# Differential_Amplifier.net
KiCad netlist of a schematic drawn in Altium Designer
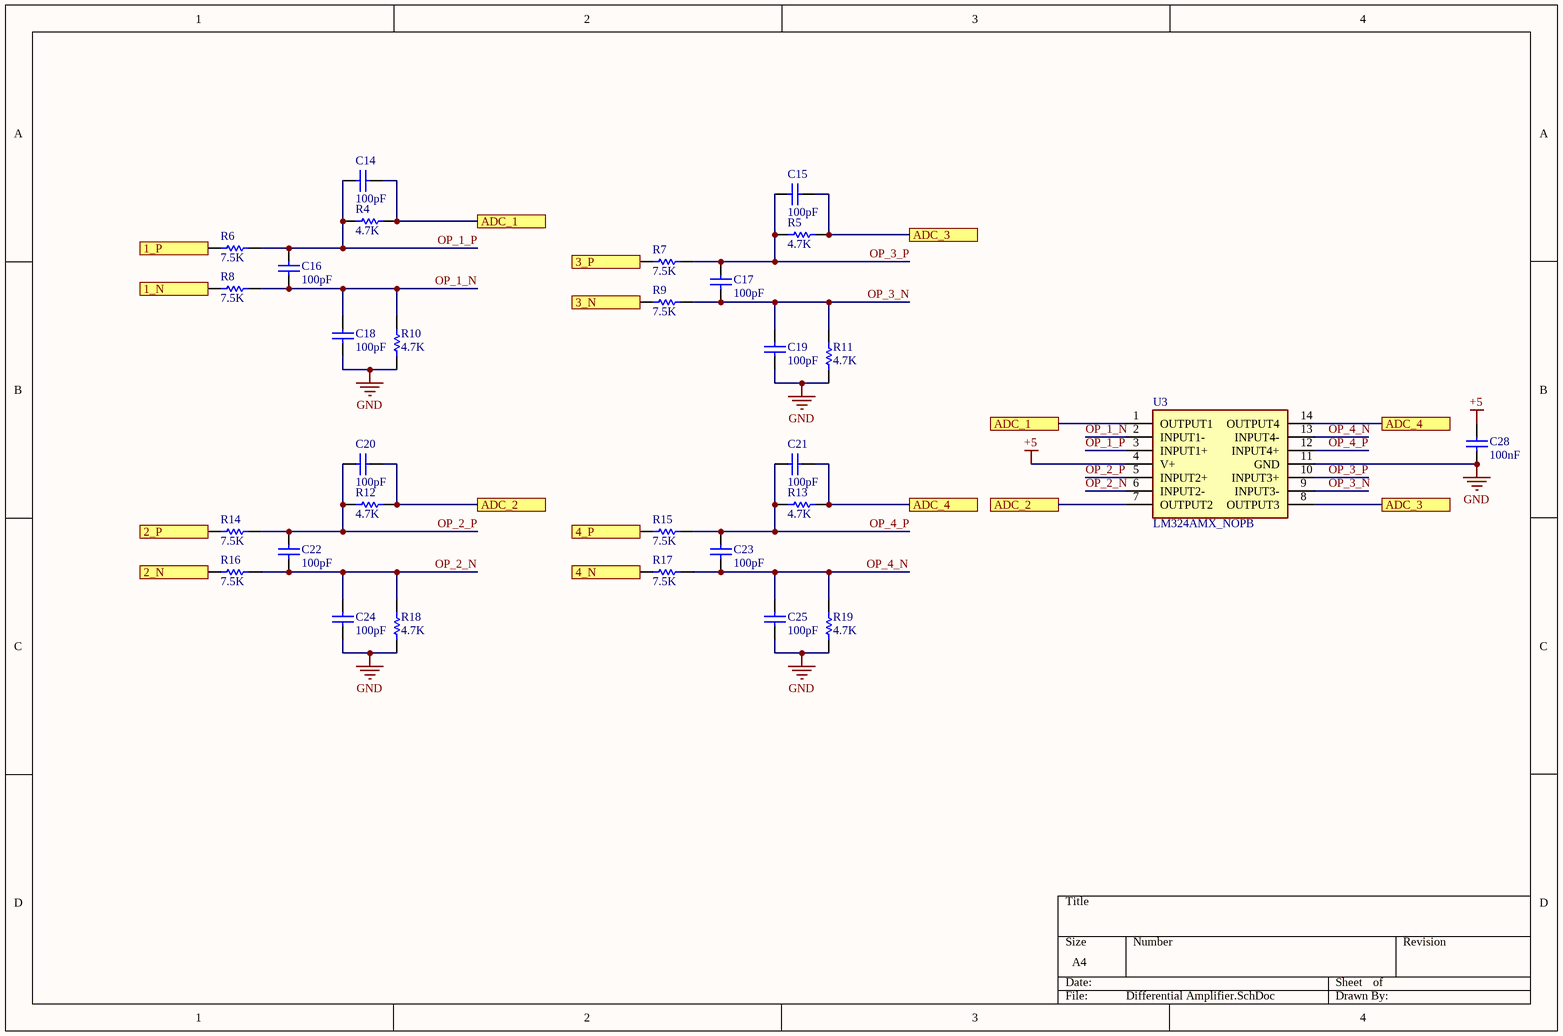
[diagram p0: Differential Amplifier.SchDoc]

(export (version "E")
  (design (tool "Eeschema 10.0.6"))
  (components
    (comp (ref "C14")
      (value "100pF")
      (footprint "C0805")
      (description "C0805C104K8RACTU. 0.1µF ±10% 10V Ceramic Capacitor X7R 0805 (2012 Metric)")
      (fields (field (name "Comment") "10V") (field (name "PUBLISHER") "Altium Limited"))
      (libsource (lib "Miscellaneous Devices") (part "Cap"))
    )
    (comp (ref "C15")
      (value "100pF")
      (footprint "C0805")
      (description "C0805C104K8RACTU. 0.1µF ±10% 10V Ceramic Capacitor X7R 0805 (2012 Metric)")
      (fields (field (name "Comment") "10V") (field (name "PUBLISHER") "Altium Limited"))
      (libsource (lib "Miscellaneous Devices") (part "Cap"))
    )
    (comp (ref "C16")
      (value "100pF")
      (footprint "C0805")
      (description "C0805C104K8RACTU. 0.1µF ±10% 10V Ceramic Capacitor X7R 0805 (2012 Metric)")
      (fields (field (name "Comment") "10V") (field (name "PUBLISHER") "Altium Limited"))
      (libsource (lib "Miscellaneous Devices") (part "Cap"))
    )
    (comp (ref "C17")
      (value "100pF")
      (footprint "C0805")
      (description "C0805C104K8RACTU. 0.1µF ±10% 10V Ceramic Capacitor X7R 0805 (2012 Metric)")
      (fields (field (name "Comment") "10V") (field (name "PUBLISHER") "Altium Limited"))
      (libsource (lib "Miscellaneous Devices") (part "Cap"))
    )
    (comp (ref "C18")
      (value "100pF")
      (footprint "C0805")
      (description "C0805C104K8RACTU. 0.1µF ±10% 10V Ceramic Capacitor X7R 0805 (2012 Metric)")
      (fields (field (name "Comment") "10V") (field (name "PUBLISHER") "Altium Limited"))
      (libsource (lib "Miscellaneous Devices") (part "Cap"))
    )
    (comp (ref "C19")
      (value "100pF")
      (footprint "C0805")
      (description "C0805C104K8RACTU. 0.1µF ±10% 10V Ceramic Capacitor X7R 0805 (2012 Metric)")
      (fields (field (name "Comment") "10V") (field (name "PUBLISHER") "Altium Limited"))
      (libsource (lib "Miscellaneous Devices") (part "Cap"))
    )
    (comp (ref "C20")
      (value "100pF")
      (footprint "C0805")
      (description "C0805C104K8RACTU. 0.1µF ±10% 10V Ceramic Capacitor X7R 0805 (2012 Metric)")
      (fields (field (name "Comment") "10V") (field (name "PUBLISHER") "Altium Limited"))
      (libsource (lib "Miscellaneous Devices") (part "Cap"))
    )
    (comp (ref "C21")
      (value "100pF")
      (footprint "C0805")
      (description "C0805C104K8RACTU. 0.1µF ±10% 10V Ceramic Capacitor X7R 0805 (2012 Metric)")
      (fields (field (name "Comment") "10V") (field (name "PUBLISHER") "Altium Limited"))
      (libsource (lib "Miscellaneous Devices") (part "Cap"))
    )
    (comp (ref "C22")
      (value "100pF")
      (footprint "C0805")
      (description "C0805C104K8RACTU. 0.1µF ±10% 10V Ceramic Capacitor X7R 0805 (2012 Metric)")
      (fields (field (name "Comment") "10V") (field (name "PUBLISHER") "Altium Limited"))
      (libsource (lib "Miscellaneous Devices") (part "Cap"))
    )
    (comp (ref "C23")
      (value "100pF")
      (footprint "C0805")
      (description "C0805C104K8RACTU. 0.1µF ±10% 10V Ceramic Capacitor X7R 0805 (2012 Metric)")
      (fields (field (name "Comment") "10V") (field (name "PUBLISHER") "Altium Limited"))
      (libsource (lib "Miscellaneous Devices") (part "Cap"))
    )
    (comp (ref "C24")
      (value "100pF")
      (footprint "C0805")
      (description "C0805C104K8RACTU. 0.1µF ±10% 10V Ceramic Capacitor X7R 0805 (2012 Metric)")
      (fields (field (name "Comment") "10V") (field (name "PUBLISHER") "Altium Limited"))
      (libsource (lib "Miscellaneous Devices") (part "Cap"))
    )
    (comp (ref "C25")
      (value "100pF")
      (footprint "C0805")
      (description "C0805C104K8RACTU. 0.1µF ±10% 10V Ceramic Capacitor X7R 0805 (2012 Metric)")
      (fields (field (name "Comment") "10V") (field (name "PUBLISHER") "Altium Limited"))
      (libsource (lib "Miscellaneous Devices") (part "Cap"))
    )
    (comp (ref "C28")
      (value "100nF")
      (footprint "C0805")
      (description "C0805C104K8RACTU. 0.1µF ±10% 10V Ceramic Capacitor X7R 0805 (2012 Metric)")
      (fields (field (name "Comment") "10V") (field (name "PUBLISHER") "Altium Limited"))
      (libsource (lib "Miscellaneous Devices") (part "Cap"))
    )
    (comp (ref "R4")
      (value "4.7K")
      (footprint "J1-0603")
      (fields (field (name "Comment") "5%") (field (name "PUBLISHER") "Altium Limited"))
      (libsource (lib "Miscellaneous Devices") (part "Res1"))
    )
    (comp (ref "R5")
      (value "4.7K")
      (footprint "J1-0603")
      (fields (field (name "Comment") "5%") (field (name "PUBLISHER") "Altium Limited"))
      (libsource (lib "Miscellaneous Devices") (part "Res1"))
    )
    (comp (ref "R6")
      (value "7.5K")
      (footprint "J1-0603")
      (fields (field (name "Comment") "5%") (field (name "PUBLISHER") "Altium Limited"))
      (libsource (lib "Miscellaneous Devices") (part "Res1"))
    )
    (comp (ref "R7")
      (value "7.5K")
      (footprint "J1-0603")
      (fields (field (name "Comment") "5%") (field (name "PUBLISHER") "Altium Limited"))
      (libsource (lib "Miscellaneous Devices") (part "Res1"))
    )
    (comp (ref "R8")
      (value "7.5K")
      (footprint "J1-0603")
      (fields (field (name "Comment") "5%") (field (name "PUBLISHER") "Altium Limited"))
      (libsource (lib "Miscellaneous Devices") (part "Res1"))
    )
    (comp (ref "R9")
      (value "7.5K")
      (footprint "J1-0603")
      (fields (field (name "Comment") "5%") (field (name "PUBLISHER") "Altium Limited"))
      (libsource (lib "Miscellaneous Devices") (part "Res1"))
    )
    (comp (ref "R10")
      (value "4.7K")
      (footprint "J1-0603")
      (fields (field (name "Comment") "5%") (field (name "PUBLISHER") "Altium Limited"))
      (libsource (lib "Miscellaneous Devices") (part "Res1"))
    )
    (comp (ref "R11")
      (value "4.7K")
      (footprint "J1-0603")
      (fields (field (name "Comment") "5%") (field (name "PUBLISHER") "Altium Limited"))
      (libsource (lib "Miscellaneous Devices") (part "Res1"))
    )
    (comp (ref "R12")
      (value "4.7K")
      (footprint "J1-0603")
      (fields (field (name "Comment") "5%") (field (name "PUBLISHER") "Altium Limited"))
      (libsource (lib "Miscellaneous Devices") (part "Res1"))
    )
    (comp (ref "R13")
      (value "4.7K")
      (footprint "J1-0603")
      (fields (field (name "Comment") "5%") (field (name "PUBLISHER") "Altium Limited"))
      (libsource (lib "Miscellaneous Devices") (part "Res1"))
    )
    (comp (ref "R14")
      (value "7.5K")
      (footprint "J1-0603")
      (fields (field (name "Comment") "5%") (field (name "PUBLISHER") "Altium Limited"))
      (libsource (lib "Miscellaneous Devices") (part "Res1"))
    )
    (comp (ref "R15")
      (value "7.5K")
      (footprint "J1-0603")
      (fields (field (name "Comment") "5%") (field (name "PUBLISHER") "Altium Limited"))
      (libsource (lib "Miscellaneous Devices") (part "Res1"))
    )
    (comp (ref "R16")
      (value "7.5K")
      (footprint "J1-0603")
      (fields (field (name "Comment") "5%") (field (name "PUBLISHER") "Altium Limited"))
      (libsource (lib "Miscellaneous Devices") (part "Res1"))
    )
    (comp (ref "R17")
      (value "7.5K")
      (footprint "J1-0603")
      (fields (field (name "Comment") "5%") (field (name "PUBLISHER") "Altium Limited"))
      (libsource (lib "Miscellaneous Devices") (part "Res1"))
    )
    (comp (ref "R18")
      (value "4.7K")
      (footprint "J1-0603")
      (fields (field (name "Comment") "5%") (field (name "PUBLISHER") "Altium Limited"))
      (libsource (lib "Miscellaneous Devices") (part "Res1"))
    )
    (comp (ref "R19")
      (value "4.7K")
      (footprint "J1-0603")
      (fields (field (name "Comment") "5%") (field (name "PUBLISHER") "Altium Limited"))
      (libsource (lib "Miscellaneous Devices") (part "Res1"))
    )
    (comp (ref "U3")
      (value "LM324AMX_NOPB")
      (footprint "SOIC127P600X175-14N - duplicate")
      (description "Integrated Circuit")
      (fields
        (field (name "MANUFACTURER_PART_NUMBER") "LM324AMX/NOPB")
        (field (name "MOUSER PART NUMBER") "926-LM324AMX/NOPB")
      )
      (libsource (lib "Motor Controller") (part "LM324AMX_NOPB"))
    )
  )
  (nets
    (net (code "1") (name "+5") (class "Default")
      (node (ref "C28") (pin "1") (pinfunction "1_1") (pintype "passive"))
      (node (ref "U3") (pin "4") (pinfunction "V+_4") (pintype "passive"))
    )
    (net (code "2") (name "/1_N") (class "Default")
      (node (ref "R8") (pin "2") (pinfunction "2_2") (pintype "passive"))
    )
    (net (code "3") (name "/1_P") (class "Default")
      (node (ref "R6") (pin "2") (pinfunction "2_2") (pintype "passive"))
    )
    (net (code "4") (name "/2_N") (class "Default")
      (node (ref "R16") (pin "2") (pinfunction "2_2") (pintype "passive"))
    )
    (net (code "5") (name "/2_P") (class "Default")
      (node (ref "R14") (pin "2") (pinfunction "2_2") (pintype "passive"))
    )
    (net (code "6") (name "/3_N") (class "Default")
      (node (ref "R9") (pin "2") (pinfunction "2_2") (pintype "passive"))
    )
    (net (code "7") (name "/3_P") (class "Default")
      (node (ref "R7") (pin "2") (pinfunction "2_2") (pintype "passive"))
    )
    (net (code "8") (name "/4_N") (class "Default")
      (node (ref "R17") (pin "2") (pinfunction "2_2") (pintype "passive"))
    )
    (net (code "9") (name "/4_P") (class "Default")
      (node (ref "R15") (pin "2") (pinfunction "2_2") (pintype "passive"))
    )
    (net (code "10") (name "/ADC_1") (class "Default")
      (node (ref "C14") (pin "2") (pinfunction "2_2") (pintype "passive"))
      (node (ref "R4") (pin "1") (pinfunction "1_1") (pintype "passive"))
      (node (ref "U3") (pin "1") (pinfunction "OUTPUT1_1") (pintype "passive"))
    )
    (net (code "11") (name "/ADC_2") (class "Default")
      (node (ref "C20") (pin "2") (pinfunction "2_2") (pintype "passive"))
      (node (ref "R12") (pin "1") (pinfunction "1_1") (pintype "passive"))
      (node (ref "U3") (pin "7") (pinfunction "OUTPUT2_7") (pintype "passive"))
    )
    (net (code "12") (name "/ADC_3") (class "Default")
      (node (ref "C15") (pin "1") (pinfunction "1_1") (pintype "passive"))
      (node (ref "R5") (pin "1") (pinfunction "1_1") (pintype "passive"))
      (node (ref "U3") (pin "8") (pinfunction "OUTPUT3_8") (pintype "passive"))
    )
    (net (code "13") (name "/ADC_4") (class "Default")
      (node (ref "C21") (pin "1") (pinfunction "1_1") (pintype "passive"))
      (node (ref "R13") (pin "1") (pinfunction "1_1") (pintype "passive"))
      (node (ref "U3") (pin "14") (pinfunction "OUTPUT4_14") (pintype "passive"))
    )
    (net (code "14") (name "/OP_1_N") (class "Default")
      (node (ref "C16") (pin "1") (pinfunction "1_1") (pintype "passive"))
      (node (ref "C18") (pin "2") (pinfunction "2_2") (pintype "passive"))
      (node (ref "R10") (pin "1") (pinfunction "1_1") (pintype "passive"))
      (node (ref "R8") (pin "1") (pinfunction "1_1") (pintype "passive"))
      (node (ref "U3") (pin "2") (pinfunction "INPUT1-_2") (pintype "passive"))
    )
    (net (code "15") (name "/OP_1_P") (class "Default")
      (node (ref "C14") (pin "1") (pinfunction "1_1") (pintype "passive"))
      (node (ref "C16") (pin "2") (pinfunction "2_2") (pintype "passive"))
      (node (ref "R4") (pin "2") (pinfunction "2_2") (pintype "passive"))
      (node (ref "R6") (pin "1") (pinfunction "1_1") (pintype "passive"))
      (node (ref "U3") (pin "3") (pinfunction "INPUT1+_3") (pintype "passive"))
    )
    (net (code "16") (name "/OP_2_N") (class "Default")
      (node (ref "C22") (pin "1") (pinfunction "1_1") (pintype "passive"))
      (node (ref "C24") (pin "2") (pinfunction "2_2") (pintype "passive"))
      (node (ref "R16") (pin "1") (pinfunction "1_1") (pintype "passive"))
      (node (ref "R18") (pin "1") (pinfunction "1_1") (pintype "passive"))
      (node (ref "U3") (pin "6") (pinfunction "INPUT2-_6") (pintype "passive"))
    )
    (net (code "17") (name "/OP_2_P") (class "Default")
      (node (ref "C20") (pin "1") (pinfunction "1_1") (pintype "passive"))
      (node (ref "C22") (pin "2") (pinfunction "2_2") (pintype "passive"))
      (node (ref "R12") (pin "2") (pinfunction "2_2") (pintype "passive"))
      (node (ref "R14") (pin "1") (pinfunction "1_1") (pintype "passive"))
      (node (ref "U3") (pin "5") (pinfunction "INPUT2+_5") (pintype "passive"))
    )
    (net (code "18") (name "/OP_3_N") (class "Default")
      (node (ref "C17") (pin "1") (pinfunction "1_1") (pintype "passive"))
      (node (ref "C19") (pin "2") (pinfunction "2_2") (pintype "passive"))
      (node (ref "R11") (pin "1") (pinfunction "1_1") (pintype "passive"))
      (node (ref "R9") (pin "1") (pinfunction "1_1") (pintype "passive"))
      (node (ref "U3") (pin "9") (pinfunction "INPUT3-_9") (pintype "passive"))
    )
    (net (code "19") (name "/OP_3_P") (class "Default")
      (node (ref "C15") (pin "2") (pinfunction "2_2") (pintype "passive"))
      (node (ref "C17") (pin "2") (pinfunction "2_2") (pintype "passive"))
      (node (ref "R5") (pin "2") (pinfunction "2_2") (pintype "passive"))
      (node (ref "R7") (pin "1") (pinfunction "1_1") (pintype "passive"))
      (node (ref "U3") (pin "10") (pinfunction "INPUT3+_10") (pintype "passive"))
    )
    (net (code "20") (name "/OP_4_N") (class "Default")
      (node (ref "C23") (pin "1") (pinfunction "1_1") (pintype "passive"))
      (node (ref "C25") (pin "2") (pinfunction "2_2") (pintype "passive"))
      (node (ref "R17") (pin "1") (pinfunction "1_1") (pintype "passive"))
      (node (ref "R19") (pin "1") (pinfunction "1_1") (pintype "passive"))
      (node (ref "U3") (pin "13") (pinfunction "INPUT4-_13") (pintype "passive"))
    )
    (net (code "21") (name "/OP_4_P") (class "Default")
      (node (ref "C21") (pin "2") (pinfunction "2_2") (pintype "passive"))
      (node (ref "C23") (pin "2") (pinfunction "2_2") (pintype "passive"))
      (node (ref "R13") (pin "2") (pinfunction "2_2") (pintype "passive"))
      (node (ref "R15") (pin "1") (pinfunction "1_1") (pintype "passive"))
      (node (ref "U3") (pin "12") (pinfunction "INPUT4+_12") (pintype "passive"))
    )
    (net (code "22") (name "GND") (class "Default")
      (node (ref "C18") (pin "1") (pinfunction "1_1") (pintype "passive"))
      (node (ref "C19") (pin "1") (pinfunction "1_1") (pintype "passive"))
      (node (ref "C24") (pin "1") (pinfunction "1_1") (pintype "passive"))
      (node (ref "C25") (pin "1") (pinfunction "1_1") (pintype "passive"))
      (node (ref "C28") (pin "2") (pinfunction "2_2") (pintype "passive"))
      (node (ref "R10") (pin "2") (pinfunction "2_2") (pintype "passive"))
      (node (ref "R11") (pin "2") (pinfunction "2_2") (pintype "passive"))
      (node (ref "R18") (pin "2") (pinfunction "2_2") (pintype "passive"))
      (node (ref "R19") (pin "2") (pinfunction "2_2") (pintype "passive"))
      (node (ref "U3") (pin "11") (pinfunction "GND_11") (pintype "passive"))
    )
  )
)
